# carrier.net
KiCad netlist of a schematic drawn in Altium Designer
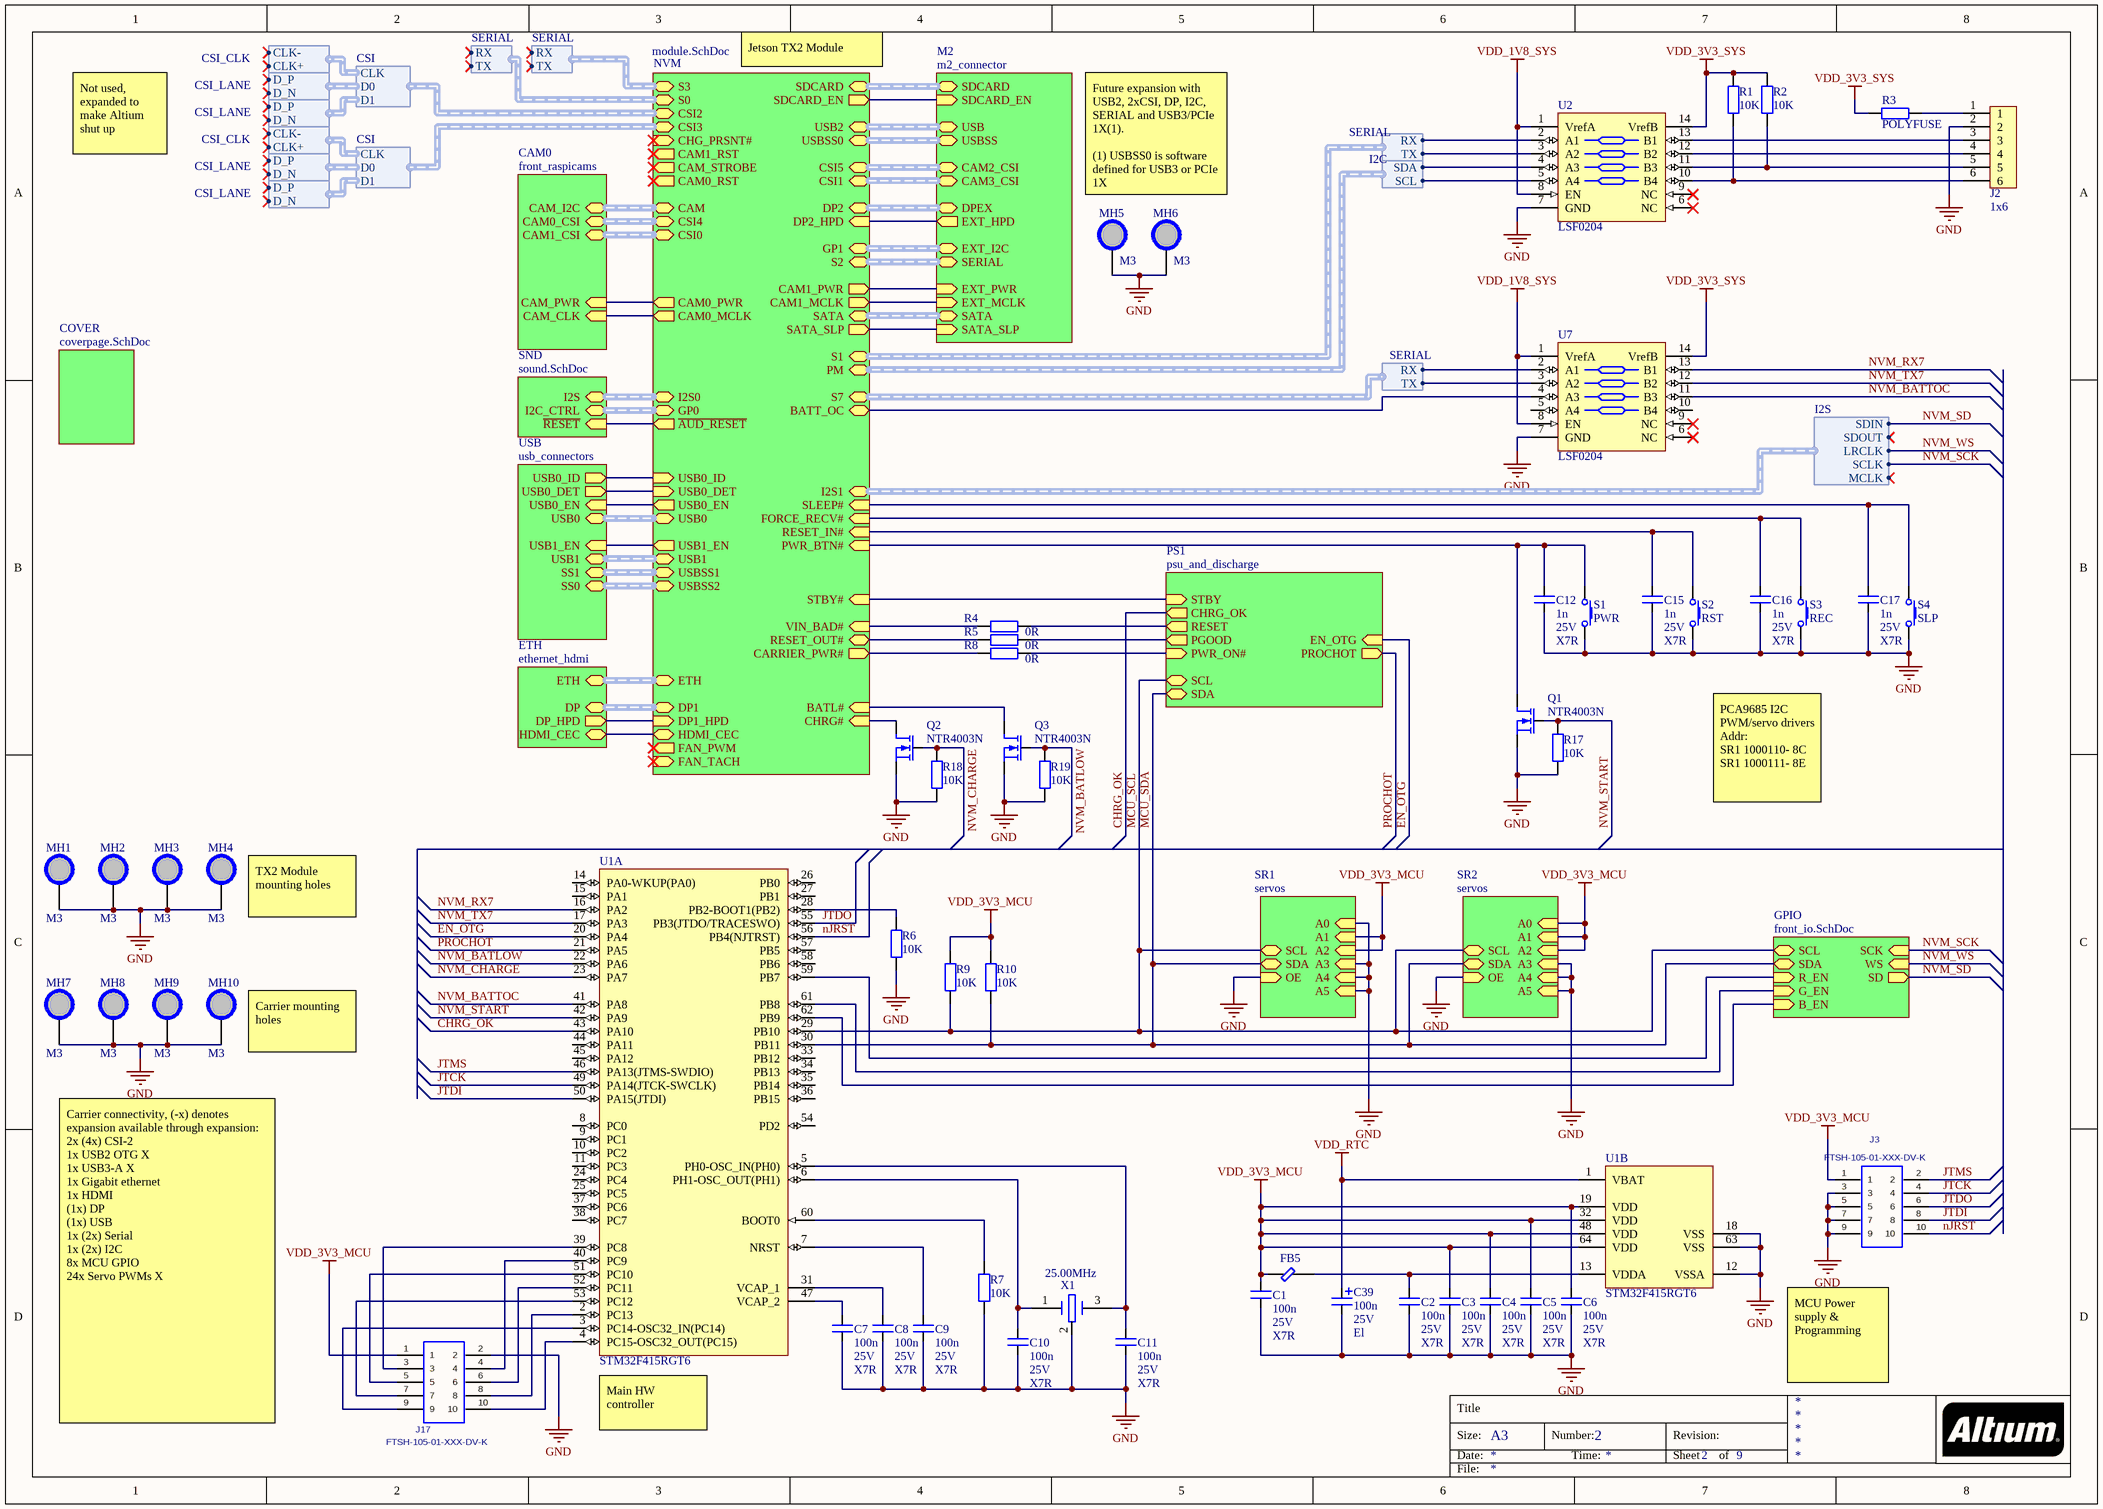
[diagram p0: carrier.SchDoc]

(export (version "E")
  (design (tool "Eeschema 10.0.6"))
  (components
    (comp (ref "C1")
      (value "100n")
      (footprint "C1005[0402]")
      (description "Capacitor")
      (fields (field (name "VOLTAGE") "25V") (field (name "TYPE") "X7R") (field (name "Comment") "cap"))
      (libsource (lib "gpa_passives") (part "cap"))
    )
    (comp (ref "C2")
      (value "100n")
      (footprint "C1005[0402]")
      (description "Capacitor")
      (fields (field (name "VOLTAGE") "25V") (field (name "TYPE") "X7R") (field (name "Comment") "cap"))
      (libsource (lib "gpa_passives") (part "cap"))
    )
    (comp (ref "C3")
      (value "100n")
      (footprint "C1005[0402]")
      (description "Capacitor")
      (fields (field (name "VOLTAGE") "25V") (field (name "TYPE") "X7R") (field (name "Comment") "cap"))
      (libsource (lib "gpa_passives") (part "cap"))
    )
    (comp (ref "C4")
      (value "100n")
      (footprint "C1005[0402]")
      (description "Capacitor")
      (fields (field (name "VOLTAGE") "25V") (field (name "TYPE") "X7R") (field (name "Comment") "cap"))
      (libsource (lib "gpa_passives") (part "cap"))
    )
    (comp (ref "C5")
      (value "100n")
      (footprint "C1005[0402]")
      (description "Capacitor")
      (fields (field (name "VOLTAGE") "25V") (field (name "TYPE") "X7R") (field (name "Comment") "cap"))
      (libsource (lib "gpa_passives") (part "cap"))
    )
    (comp (ref "C6")
      (value "100n")
      (footprint "C1005[0402]")
      (description "Capacitor")
      (fields (field (name "VOLTAGE") "25V") (field (name "TYPE") "X7R") (field (name "Comment") "cap"))
      (libsource (lib "gpa_passives") (part "cap"))
    )
    (comp (ref "C7")
      (value "100n")
      (footprint "C1005[0402]")
      (description "Capacitor")
      (fields (field (name "VOLTAGE") "25V") (field (name "TYPE") "X7R") (field (name "Comment") "cap"))
      (libsource (lib "gpa_passives") (part "cap"))
    )
    (comp (ref "C8")
      (value "100n")
      (footprint "C1005[0402]")
      (description "Capacitor")
      (fields (field (name "VOLTAGE") "25V") (field (name "TYPE") "X7R") (field (name "Comment") "cap"))
      (libsource (lib "gpa_passives") (part "cap"))
    )
    (comp (ref "C9")
      (value "100n")
      (footprint "C1005[0402]")
      (description "Capacitor")
      (fields (field (name "VOLTAGE") "25V") (field (name "TYPE") "X7R") (field (name "Comment") "cap"))
      (libsource (lib "gpa_passives") (part "cap"))
    )
    (comp (ref "C10")
      (value "100n")
      (footprint "C1005[0402]")
      (description "Capacitor")
      (fields (field (name "VOLTAGE") "25V") (field (name "TYPE") "X7R") (field (name "Comment") "cap"))
      (libsource (lib "gpa_passives") (part "cap"))
    )
    (comp (ref "C11")
      (value "100n")
      (footprint "C1005[0402]")
      (description "Capacitor")
      (fields (field (name "VOLTAGE") "25V") (field (name "TYPE") "X7R") (field (name "Comment") "cap"))
      (libsource (lib "gpa_passives") (part "cap"))
    )
    (comp (ref "C12")
      (value "1n")
      (footprint "C1005[0402]")
      (description "Capacitor")
      (fields (field (name "VOLTAGE") "25V") (field (name "TYPE") "X7R") (field (name "Comment") "cap"))
      (libsource (lib "gpa_passives") (part "cap"))
    )
    (comp (ref "C15")
      (value "1n")
      (footprint "C1005[0402]")
      (description "Capacitor")
      (fields (field (name "VOLTAGE") "25V") (field (name "TYPE") "X7R") (field (name "Comment") "cap"))
      (libsource (lib "gpa_passives") (part "cap"))
    )
    (comp (ref "C16")
      (value "1n")
      (footprint "C1005[0402]")
      (description "Capacitor")
      (fields (field (name "VOLTAGE") "25V") (field (name "TYPE") "X7R") (field (name "Comment") "cap"))
      (libsource (lib "gpa_passives") (part "cap"))
    )
    (comp (ref "C17")
      (value "1n")
      (footprint "C1005[0402]")
      (description "Capacitor")
      (fields (field (name "VOLTAGE") "25V") (field (name "TYPE") "X7R") (field (name "Comment") "cap"))
      (libsource (lib "gpa_passives") (part "cap"))
    )
    (comp (ref "C39")
      (value "100n")
      (footprint "SC_FCS0H473ZFTBR24")
      (description "Polarized capacitor")
      (fields (field (name "VOLTAGE") "25V") (field (name "TYPE") "El") (field (name "Comment") "pcap"))
      (libsource (lib "gpa_passives") (part "pcap"))
    )
    (comp (ref "FB5")
      (value "2506036007Y3")
      (footprint "FBC1608X07N")
      (description "Ferrite bead")
      (libsource (lib "gpa_passives") (part "ferrite_bead"))
    )
    (comp (ref "J2")
      (value "1x6")
      (footprint "hdr_100mil_1x6")
      (libsource (lib "gpa_connectors") (part "header_1x6"))
    )
    (comp (ref "J3")
      (value "FTSH-105-01-XXX-DV-K")
      (footprint "FTSH-105-01-XXX-DV-K")
      (description "TERMINAL STRIP, .050\"(1.27mm) PITCH, 10 PINS, KEYED")
      (fields (field (name "MANUFACTURER") "SAMTEC") (field (name "CREATED") "November 30, 2016 - Wendy Xin"))
      (libsource (lib "FTSH-105-01-XXX-DV-K") (part "FTSH-105-01-XXX-DV-K"))
    )
    (comp (ref "J17")
      (value "FTSH-105-01-XXX-DV-K")
      (footprint "FTSH-105-01-XXX-DV-K")
      (description "TERMINAL STRIP, .050\"(1.27mm) PITCH, 10 PINS, KEYED")
      (fields (field (name "MANUFACTURER") "SAMTEC") (field (name "CREATED") "November 30, 2016 - Wendy Xin"))
      (libsource (lib "FTSH-105-01-XXX-DV-K") (part "FTSH-105-01-XXX-DV-K"))
    )
    (comp (ref "MH1")
      (value "M3")
      (footprint "m2_pan_loose_round")
      (libsource (lib "gpa_mounting") (part "mounting_hole"))
    )
    (comp (ref "MH2")
      (value "M3")
      (footprint "m2_pan_loose_round")
      (libsource (lib "gpa_mounting") (part "mounting_hole"))
    )
    (comp (ref "MH3")
      (value "M3")
      (footprint "m2_pan_loose_round")
      (libsource (lib "gpa_mounting") (part "mounting_hole"))
    )
    (comp (ref "MH4")
      (value "M3")
      (footprint "m2_pan_loose_round")
      (libsource (lib "gpa_mounting") (part "mounting_hole"))
    )
    (comp (ref "MH5")
      (value "M3")
      (footprint "m2_pan_loose_round")
      (libsource (lib "gpa_mounting") (part "mounting_hole"))
    )
    (comp (ref "MH6")
      (value "M3")
      (footprint "m2_pan_loose_round")
      (libsource (lib "gpa_mounting") (part "mounting_hole"))
    )
    (comp (ref "MH7")
      (value "M3")
      (footprint "m2_pan_loose_round")
      (libsource (lib "gpa_mounting") (part "mounting_hole"))
    )
    (comp (ref "MH8")
      (value "M3")
      (footprint "m2_pan_loose_round")
      (libsource (lib "gpa_mounting") (part "mounting_hole"))
    )
    (comp (ref "MH9")
      (value "M3")
      (footprint "m2_pan_loose_round")
      (libsource (lib "gpa_mounting") (part "mounting_hole"))
    )
    (comp (ref "MH10")
      (value "M3")
      (footprint "m2_pan_loose_round")
      (libsource (lib "gpa_mounting") (part "mounting_hole"))
    )
    (comp (ref "Q1")
      (value "NTR4003N")
      (footprint "NCH_SOT95P237X110-3N")
      (libsource (lib "gpa_actives") (part "nch_mosfet"))
    )
    (comp (ref "Q2")
      (value "NTR4003N")
      (footprint "NCH_SOT95P237X110-3N")
      (libsource (lib "gpa_actives") (part "nch_mosfet"))
    )
    (comp (ref "Q3")
      (value "NTR4003N")
      (footprint "NCH_SOT95P237X110-3N")
      (libsource (lib "gpa_actives") (part "nch_mosfet"))
    )
    (comp (ref "R1")
      (value "10K")
      (footprint "R1005[0402]")
      (description "Resistor")
      (fields (field (name "Comment") "res"))
      (libsource (lib "gpa_passives") (part "res"))
    )
    (comp (ref "R2")
      (value "10K")
      (footprint "R1005[0402]")
      (description "Resistor")
      (fields (field (name "Comment") "res"))
      (libsource (lib "gpa_passives") (part "res"))
    )
    (comp (ref "R3")
      (value "POLYFUSE")
      (footprint "R1005[0402]")
      (description "Resistor")
      (fields (field (name "Comment") "res"))
      (libsource (lib "") (part "res_2"))
    )
    (comp (ref "R4")
      (value "0R")
      (footprint "R1005[0402]")
      (description "Resistor")
      (fields (field (name "Comment") "res"))
      (libsource (lib "gpa_passives") (part "res"))
    )
    (comp (ref "R5")
      (value "0R")
      (footprint "R1005[0402]")
      (description "Resistor")
      (fields (field (name "Comment") "res"))
      (libsource (lib "gpa_passives") (part "res"))
    )
    (comp (ref "R6")
      (value "10K")
      (footprint "R1005[0402]")
      (description "Resistor")
      (fields (field (name "Comment") "res"))
      (libsource (lib "") (part "res_1"))
    )
    (comp (ref "R7")
      (value "10K")
      (footprint "R1005[0402]")
      (description "Resistor")
      (fields (field (name "Comment") "res"))
      (libsource (lib "") (part "res_1"))
    )
    (comp (ref "R8")
      (value "0R")
      (footprint "R1005[0402]")
      (description "Resistor")
      (fields (field (name "Comment") "res"))
      (libsource (lib "gpa_passives") (part "res"))
    )
    (comp (ref "R9")
      (value "10K")
      (footprint "R1005[0402]")
      (description "Resistor")
      (fields (field (name "Comment") "res"))
      (libsource (lib "") (part "res_1"))
    )
    (comp (ref "R10")
      (value "10K")
      (footprint "R1005[0402]")
      (description "Resistor")
      (fields (field (name "Comment") "res"))
      (libsource (lib "") (part "res_1"))
    )
    (comp (ref "R17")
      (value "10K")
      (footprint "R1005[0402]")
      (description "Resistor")
      (fields (field (name "Comment") "res"))
      (libsource (lib "") (part "res_1"))
    )
    (comp (ref "R18")
      (value "10K")
      (footprint "R1005[0402]")
      (description "Resistor")
      (fields (field (name "Comment") "res"))
      (libsource (lib "") (part "res_1"))
    )
    (comp (ref "R19")
      (value "10K")
      (footprint "R1005[0402]")
      (description "Resistor")
      (fields (field (name "Comment") "res"))
      (libsource (lib "") (part "res_1"))
    )
    (comp (ref "S1")
      (value "btn")
      (footprint "SW_6MM_TACT")
      (fields (field (name "TEXT") "PWR"))
      (libsource (lib "gpa_passives") (part "btn"))
    )
    (comp (ref "S2")
      (value "btn")
      (footprint "SW_6MM_TACT")
      (fields (field (name "TEXT") "RST"))
      (libsource (lib "gpa_passives") (part "btn"))
    )
    (comp (ref "S3")
      (value "btn")
      (footprint "SW_6MM_TACT")
      (fields (field (name "TEXT") "REC"))
      (libsource (lib "gpa_passives") (part "btn"))
    )
    (comp (ref "S4")
      (value "btn")
      (footprint "SW_6MM_TACT")
      (fields (field (name "TEXT") "SLP"))
      (libsource (lib "gpa_passives") (part "btn"))
    )
    (comp (ref "U1")
      (value "STM32F415RGT6")
      (footprint "STM-LQFP64_N")
      (fields (field (name "MANUFACTURER") "STMicroelectronics"))
      (libsource (lib "STMicroelectronics STM32 F4") (part "STM32F415RGT6"))
    )
    (comp (ref "U2")
      (value "LSF0204")
      (footprint "TI_TSOP65P640X120-14N")
      (libsource (lib "gpa_ti") (part "lsf0204"))
    )
    (comp (ref "U7")
      (value "LSF0204")
      (footprint "TI_TSOP65P640X120-14N")
      (libsource (lib "gpa_ti") (part "lsf0204"))
    )
    (comp (ref "X1")
      (value "25.00MHz")
      (footprint "FA-238")
      (description "Crystal with shield")
      (fields (field (name "Comment") "crystal_shielded"))
      (libsource (lib "gpa_passives") (part "crystal_shielded"))
    )
  )
  (nets
    (net (code "6") (name "/BATL#") (class "Default")
      (node (ref "Q3") (pin "D") (pinfunction "D_D") (pintype "passive"))
    )
    (net (code "7") (name "/BATT_OC") (class "Default")
      (node (ref "U7") (pin "4") (pinfunction "A3_4") (pintype "bidirectional"))
    )
    (net (code "8") (name "/B_EN") (class "Default")
      (node (ref "U1") (pin "62") (pinfunction "PB9_62") (pintype "bidirectional"))
    )
    (net (code "21") (name "/CARRIER_PWR#") (class "Default")
      (node (ref "R8") (pin "1") (pinfunction "1_1") (pintype "passive"))
    )
    (net (code "23") (name "/CHRG#") (class "Default")
      (node (ref "Q2") (pin "D") (pinfunction "D_D") (pintype "passive"))
    )
    (net (code "24") (name "/CHRG_OK") (class "Default")
      (node (ref "U1") (pin "43") (pinfunction "PA10_43") (pintype "bidirectional"))
    )
    (net (code "29") (name "/EN_OTG") (class "Default")
      (node (ref "U1") (pin "20") (pinfunction "PA4_20") (pintype "bidirectional"))
    )
    (net (code "35") (name "/FORCE_RECV#") (class "Default")
      (node (ref "C16") (pin "2") (pinfunction "2_2") (pintype "passive"))
      (node (ref "S3") (pin "1") (pinfunction "1_1") (pintype "passive"))
    )
    (net (code "37") (name "/G_EN") (class "Default")
      (node (ref "U1") (pin "61") (pinfunction "PB8_61") (pintype "bidirectional"))
    )
    (net (code "40") (name "/JTCK") (class "Default")
      (node (ref "J3") (pin "4") (pinfunction "4_4") (pintype "passive"))
      (node (ref "U1") (pin "49") (pinfunction "PA14(JTCK-SWCLK)_49") (pintype "bidirectional"))
    )
    (net (code "41") (name "/JTDI") (class "Default")
      (node (ref "J3") (pin "8") (pinfunction "8_8") (pintype "passive"))
      (node (ref "U1") (pin "50") (pinfunction "PA15(JTDI)_50") (pintype "bidirectional"))
    )
    (net (code "42") (name "/JTDO") (class "Default")
      (node (ref "J3") (pin "6") (pinfunction "6_6") (pintype "passive"))
      (node (ref "U1") (pin "55") (pinfunction "PB3(JTDO/TRACESWO)_55") (pintype "bidirectional"))
    )
    (net (code "43") (name "/JTMS") (class "Default")
      (node (ref "J3") (pin "2") (pinfunction "2_2") (pintype "passive"))
      (node (ref "U1") (pin "46") (pinfunction "PA13(JTMS-SWDIO)_46") (pintype "bidirectional"))
    )
    (net (code "44") (name "/MCU_SCL") (class "Default")
      (node (ref "R9") (pin "1") (pinfunction "1_1") (pintype "passive"))
      (node (ref "U1") (pin "29") (pinfunction "PB10_29") (pintype "bidirectional"))
    )
    (net (code "45") (name "/MCU_SDA") (class "Default")
      (node (ref "R10") (pin "1") (pinfunction "1_1") (pintype "passive"))
      (node (ref "U1") (pin "30") (pinfunction "PB11_30") (pintype "bidirectional"))
    )
    (net (code "46") (name "/NVM_BATLOW") (class "Default")
      (node (ref "Q3") (pin "G") (pinfunction "G_G") (pintype "passive"))
      (node (ref "R19") (pin "2") (pinfunction "2_2") (pintype "passive"))
      (node (ref "U1") (pin "22") (pinfunction "PA6_22") (pintype "bidirectional"))
    )
    (net (code "47") (name "/NVM_BATTOC") (class "Default")
      (node (ref "U1") (pin "41") (pinfunction "PA8_41") (pintype "bidirectional"))
      (node (ref "U7") (pin "11") (pinfunction "B3_11") (pintype "bidirectional"))
    )
    (net (code "48") (name "/NVM_CHARGE") (class "Default")
      (node (ref "Q2") (pin "G") (pinfunction "G_G") (pintype "passive"))
      (node (ref "R18") (pin "2") (pinfunction "2_2") (pintype "passive"))
      (node (ref "U1") (pin "23") (pinfunction "PA7_23") (pintype "bidirectional"))
    )
    (net (code "49") (name "/NVM_RX7") (class "Default")
      (node (ref "U1") (pin "16") (pinfunction "PA2_16") (pintype "bidirectional"))
      (node (ref "U7") (pin "13") (pinfunction "B1_13") (pintype "bidirectional"))
    )
    (net (code "52") (name "/NVM_START") (class "Default")
      (node (ref "Q1") (pin "G") (pinfunction "G_G") (pintype "passive"))
      (node (ref "R17") (pin "2") (pinfunction "2_2") (pintype "passive"))
      (node (ref "U1") (pin "42") (pinfunction "PA9_42") (pintype "bidirectional"))
    )
    (net (code "53") (name "/NVM_TX7") (class "Default")
      (node (ref "U1") (pin "17") (pinfunction "PA3_17") (pintype "bidirectional"))
      (node (ref "U7") (pin "12") (pinfunction "B2_12") (pintype "bidirectional"))
    )
    (net (code "55") (name "/PGOOD") (class "Default")
      (node (ref "R5") (pin "2") (pinfunction "2_2") (pintype "passive"))
    )
    (net (code "56") (name "/PROCHOT") (class "Default")
      (node (ref "U1") (pin "21") (pinfunction "PA5_21") (pintype "bidirectional"))
    )
    (net (code "57") (name "/PWR_BTN#") (class "Default")
      (node (ref "C12") (pin "2") (pinfunction "2_2") (pintype "passive"))
      (node (ref "Q1") (pin "D") (pinfunction "D_D") (pintype "passive"))
      (node (ref "S1") (pin "1") (pinfunction "1_1") (pintype "passive"))
    )
    (net (code "58") (name "/PWR_ON#") (class "Default")
      (node (ref "R8") (pin "2") (pinfunction "2_2") (pintype "passive"))
    )
    (net (code "59") (name "/RESET") (class "Default")
      (node (ref "R4") (pin "2") (pinfunction "2_2") (pintype "passive"))
    )
    (net (code "60") (name "/RESET_IN#") (class "Default")
      (node (ref "C15") (pin "2") (pinfunction "2_2") (pintype "passive"))
      (node (ref "S2") (pin "1") (pinfunction "1_1") (pintype "passive"))
    )
    (net (code "61") (name "/RESET_OUT#") (class "Default")
      (node (ref "R5") (pin "1") (pinfunction "1_1") (pintype "passive"))
    )
    (net (code "62") (name "/R_EN") (class "Default")
      (node (ref "U1") (pin "59") (pinfunction "PB7_59") (pintype "bidirectional"))
    )
    (net (code "69") (name "/SLEEP#") (class "Default")
      (node (ref "C17") (pin "2") (pinfunction "2_2") (pintype "passive"))
      (node (ref "S4") (pin "1") (pinfunction "1_1") (pintype "passive"))
    )
    (net (code "81") (name "/VIN_BAD#") (class "Default")
      (node (ref "R4") (pin "1") (pinfunction "1_1") (pintype "passive"))
    )
    (net (code "82") (name "/nJRST") (class "Default")
      (node (ref "J3") (pin "10") (pinfunction "10_10") (pintype "passive"))
      (node (ref "U1") (pin "56") (pinfunction "PB4(NJTRST)_56") (pintype "bidirectional"))
    )
    (net (code "87") (name "GND") (class "Default")
      (node (ref "C1") (pin "2") (pinfunction "2_2") (pintype "passive"))
      (node (ref "C10") (pin "2") (pinfunction "2_2") (pintype "passive"))
      (node (ref "C11") (pin "2") (pinfunction "2_2") (pintype "passive"))
      (node (ref "C12") (pin "1") (pinfunction "1_1") (pintype "passive"))
      (node (ref "C15") (pin "1") (pinfunction "1_1") (pintype "passive"))
      (node (ref "C16") (pin "1") (pinfunction "1_1") (pintype "passive"))
      (node (ref "C17") (pin "1") (pinfunction "1_1") (pintype "passive"))
      (node (ref "C2") (pin "2") (pinfunction "2_2") (pintype "passive"))
      (node (ref "C3") (pin "2") (pinfunction "2_2") (pintype "passive"))
      (node (ref "C39") (pin "2") (pinfunction "2_2") (pintype "passive"))
      (node (ref "C4") (pin "2") (pinfunction "2_2") (pintype "passive"))
      (node (ref "C5") (pin "2") (pinfunction "2_2") (pintype "passive"))
      (node (ref "C6") (pin "2") (pinfunction "2_2") (pintype "passive"))
      (node (ref "C7") (pin "2") (pinfunction "2_2") (pintype "passive"))
      (node (ref "C8") (pin "2") (pinfunction "2_2") (pintype "passive"))
      (node (ref "C9") (pin "2") (pinfunction "2_2") (pintype "passive"))
      (node (ref "J17") (pin "2") (pinfunction "2_2") (pintype "passive"))
      (node (ref "J2") (pin "2") (pinfunction "2_2") (pintype "passive"))
      (node (ref "J3") (pin "3") (pinfunction "3_3") (pintype "passive"))
      (node (ref "J3") (pin "5") (pinfunction "5_5") (pintype "passive"))
      (node (ref "J3") (pin "7") (pinfunction "7_7") (pintype "passive"))
      (node (ref "J3") (pin "9") (pinfunction "9_9") (pintype "passive"))
      (node (ref "MH1") (pin "1") (pinfunction "1_1") (pintype "passive"))
      (node (ref "MH10") (pin "1") (pinfunction "1_1") (pintype "passive"))
      (node (ref "MH2") (pin "1") (pinfunction "1_1") (pintype "passive"))
      (node (ref "MH3") (pin "1") (pinfunction "1_1") (pintype "passive"))
      (node (ref "MH4") (pin "1") (pinfunction "1_1") (pintype "passive"))
      (node (ref "MH5") (pin "1") (pinfunction "1_1") (pintype "passive"))
      (node (ref "MH6") (pin "1") (pinfunction "1_1") (pintype "passive"))
      (node (ref "MH7") (pin "1") (pinfunction "1_1") (pintype "passive"))
      (node (ref "MH8") (pin "1") (pinfunction "1_1") (pintype "passive"))
      (node (ref "MH9") (pin "1") (pinfunction "1_1") (pintype "passive"))
      (node (ref "Q1") (pin "S") (pinfunction "S_S") (pintype "passive"))
      (node (ref "Q2") (pin "S") (pinfunction "S_S") (pintype "passive"))
      (node (ref "Q3") (pin "S") (pinfunction "S_S") (pintype "passive"))
      (node (ref "R17") (pin "1") (pinfunction "1_1") (pintype "passive"))
      (node (ref "R18") (pin "1") (pinfunction "1_1") (pintype "passive"))
      (node (ref "R19") (pin "1") (pinfunction "1_1") (pintype "passive"))
      (node (ref "R6") (pin "1") (pinfunction "1_1") (pintype "passive"))
      (node (ref "R7") (pin "1") (pinfunction "1_1") (pintype "passive"))
      (node (ref "S1") (pin "2") (pinfunction "2_2") (pintype "passive"))
      (node (ref "S2") (pin "2") (pinfunction "2_2") (pintype "passive"))
      (node (ref "S3") (pin "2") (pinfunction "2_2") (pintype "passive"))
      (node (ref "S4") (pin "2") (pinfunction "2_2") (pintype "passive"))
      (node (ref "U1") (pin "12") (pinfunction "VSSA_12") (pintype "power_in"))
      (node (ref "U1") (pin "18") (pinfunction "VSS_18") (pintype "power_in"))
      (node (ref "U1") (pin "63") (pinfunction "VSS_63") (pintype "power_in"))
      (node (ref "U2") (pin "7") (pinfunction "GND_7") (pintype "power_in"))
      (node (ref "U7") (pin "7") (pinfunction "GND_7") (pintype "power_in"))
      (node (ref "X1") (pin "2") (pinfunction "2_2") (pintype "passive"))
    )
    (net (code "88") (name "Net-(J2-Pad1)") (class "Default")
      (node (ref "J2") (pin "1") (pinfunction "1_1") (pintype "passive"))
      (node (ref "R3") (pin "1") (pinfunction "1_1") (pintype "passive"))
    )
    (net (code "89") (name "Net-(U1A-BOOT0)") (class "Default")
      (node (ref "R7") (pin "2") (pinfunction "2_2") (pintype "passive"))
      (node (ref "U1") (pin "60") (pinfunction "BOOT0_60") (pintype "input"))
    )
    (net (code "90") (name "Net-(U1A-NRST)") (class "Default")
      (node (ref "C9") (pin "1") (pinfunction "1_1") (pintype "passive"))
      (node (ref "U1") (pin "7") (pinfunction "NRST_7") (pintype "bidirectional"))
    )
    (net (code "91") (name "Net-(U1A-PB2-BOOT1(PB2))") (class "Default")
      (node (ref "R6") (pin "2") (pinfunction "2_2") (pintype "passive"))
      (node (ref "U1") (pin "28") (pinfunction "PB2-BOOT1(PB2)_28") (pintype "bidirectional"))
    )
    (net (code "92") (name "Net-(U1A-PC8)") (class "Default")
      (node (ref "J17") (pin "3") (pinfunction "3_3") (pintype "passive"))
      (node (ref "U1") (pin "39") (pinfunction "PC8_39") (pintype "bidirectional"))
    )
    (net (code "93") (name "Net-(U1A-PC9)") (class "Default")
      (node (ref "J17") (pin "4") (pinfunction "4_4") (pintype "passive"))
      (node (ref "U1") (pin "40") (pinfunction "PC9_40") (pintype "bidirectional"))
    )
    (net (code "94") (name "Net-(U1A-PC10)") (class "Default")
      (node (ref "J17") (pin "5") (pinfunction "5_5") (pintype "passive"))
      (node (ref "U1") (pin "51") (pinfunction "PC10_51") (pintype "bidirectional"))
    )
    (net (code "95") (name "Net-(U1A-PC11)") (class "Default")
      (node (ref "J17") (pin "6") (pinfunction "6_6") (pintype "passive"))
      (node (ref "U1") (pin "52") (pinfunction "PC11_52") (pintype "bidirectional"))
    )
    (net (code "96") (name "Net-(U1A-PC12)") (class "Default")
      (node (ref "J17") (pin "7") (pinfunction "7_7") (pintype "passive"))
      (node (ref "U1") (pin "53") (pinfunction "PC12_53") (pintype "bidirectional"))
    )
    (net (code "97") (name "Net-(U1A-PC13)") (class "Default")
      (node (ref "J17") (pin "8") (pinfunction "8_8") (pintype "passive"))
      (node (ref "U1") (pin "2") (pinfunction "PC13_2") (pintype "bidirectional"))
    )
    (net (code "98") (name "Net-(U1A-PC14-OSC32_IN(PC14))") (class "Default")
      (node (ref "J17") (pin "9") (pinfunction "9_9") (pintype "passive"))
      (node (ref "U1") (pin "3") (pinfunction "PC14-OSC32_IN(PC14)_3") (pintype "bidirectional"))
    )
    (net (code "99") (name "Net-(U1A-PC15-OSC32_OUT(PC15))") (class "Default")
      (node (ref "J17") (pin "10") (pinfunction "10_10") (pintype "passive"))
      (node (ref "U1") (pin "4") (pinfunction "PC15-OSC32_OUT(PC15)_4") (pintype "bidirectional"))
    )
    (net (code "100") (name "Net-(U1A-PH0-OSC_IN(PH0))") (class "Default")
      (node (ref "C11") (pin "1") (pinfunction "1_1") (pintype "passive"))
      (node (ref "U1") (pin "5") (pinfunction "PH0-OSC_IN(PH0)_5") (pintype "bidirectional"))
      (node (ref "X1") (pin "3") (pinfunction "3_3") (pintype "passive"))
    )
    (net (code "101") (name "Net-(U1A-PH1-OSC_OUT(PH1))") (class "Default")
      (node (ref "C10") (pin "1") (pinfunction "1_1") (pintype "passive"))
      (node (ref "U1") (pin "6") (pinfunction "PH1-OSC_OUT(PH1)_6") (pintype "bidirectional"))
      (node (ref "X1") (pin "1") (pinfunction "1_1") (pintype "passive"))
    )
    (net (code "102") (name "Net-(U1A-VCAP_1)") (class "Default")
      (node (ref "C8") (pin "1") (pinfunction "1_1") (pintype "passive"))
      (node (ref "U1") (pin "31") (pinfunction "VCAP_1_31") (pintype "power_in"))
    )
    (net (code "103") (name "Net-(U1A-VCAP_2)") (class "Default")
      (node (ref "C7") (pin "1") (pinfunction "1_1") (pintype "passive"))
      (node (ref "U1") (pin "47") (pinfunction "VCAP_2_47") (pintype "power_in"))
    )
    (net (code "104") (name "Net-(U1B-VDDA)") (class "Default")
      (node (ref "C2") (pin "1") (pinfunction "1_1") (pintype "passive"))
      (node (ref "FB5") (pin "2") (pinfunction "2_2") (pintype "passive"))
      (node (ref "U1") (pin "13") (pinfunction "VDDA_13") (pintype "power_in"))
    )
    (net (code "105") (name "Net-(U2-B1)") (class "Default")
      (node (ref "J2") (pin "3") (pinfunction "3_3") (pintype "passive"))
      (node (ref "U2") (pin "13") (pinfunction "B1_13") (pintype "bidirectional"))
    )
    (net (code "106") (name "Net-(U2-B2)") (class "Default")
      (node (ref "J2") (pin "4") (pinfunction "4_4") (pintype "passive"))
      (node (ref "U2") (pin "12") (pinfunction "B2_12") (pintype "bidirectional"))
    )
    (net (code "107") (name "Net-(U2-B3)") (class "Default")
      (node (ref "J2") (pin "5") (pinfunction "5_5") (pintype "passive"))
      (node (ref "R2") (pin "1") (pinfunction "1_1") (pintype "passive"))
      (node (ref "U2") (pin "11") (pinfunction "B3_11") (pintype "bidirectional"))
    )
    (net (code "108") (name "Net-(U2-B4)") (class "Default")
      (node (ref "J2") (pin "6") (pinfunction "6_6") (pintype "passive"))
      (node (ref "R1") (pin "1") (pinfunction "1_1") (pintype "passive"))
      (node (ref "U2") (pin "10") (pinfunction "B4_10") (pintype "bidirectional"))
    )
    (net (code "109") (name "VDD_1V8_SYS") (class "Default")
      (node (ref "U2") (pin "1") (pinfunction "VrefA_1") (pintype "power_in"))
      (node (ref "U2") (pin "8") (pinfunction "EN_8") (pintype "input"))
      (node (ref "U7") (pin "1") (pinfunction "VrefA_1") (pintype "power_in"))
      (node (ref "U7") (pin "8") (pinfunction "EN_8") (pintype "input"))
    )
    (net (code "110") (name "VDD_3V3_MCU") (class "Default")
      (node (ref "C1") (pin "1") (pinfunction "1_1") (pintype "passive"))
      (node (ref "C3") (pin "1") (pinfunction "1_1") (pintype "passive"))
      (node (ref "C4") (pin "1") (pinfunction "1_1") (pintype "passive"))
      (node (ref "C5") (pin "1") (pinfunction "1_1") (pintype "passive"))
      (node (ref "C6") (pin "1") (pinfunction "1_1") (pintype "passive"))
      (node (ref "FB5") (pin "1") (pinfunction "1_1") (pintype "passive"))
      (node (ref "J17") (pin "1") (pinfunction "1_1") (pintype "passive"))
      (node (ref "J3") (pin "1") (pinfunction "1_1") (pintype "passive"))
      (node (ref "R10") (pin "2") (pinfunction "2_2") (pintype "passive"))
      (node (ref "R9") (pin "2") (pinfunction "2_2") (pintype "passive"))
      (node (ref "U1") (pin "19") (pinfunction "VDD_19") (pintype "power_in"))
      (node (ref "U1") (pin "32") (pinfunction "VDD_32") (pintype "power_in"))
      (node (ref "U1") (pin "48") (pinfunction "VDD_48") (pintype "power_in"))
      (node (ref "U1") (pin "64") (pinfunction "VDD_64") (pintype "power_in"))
    )
    (net (code "111") (name "VDD_3V3_SYS") (class "Default")
      (node (ref "R1") (pin "2") (pinfunction "2_2") (pintype "passive"))
      (node (ref "R2") (pin "2") (pinfunction "2_2") (pintype "passive"))
      (node (ref "R3") (pin "2") (pinfunction "2_2") (pintype "passive"))
      (node (ref "U2") (pin "14") (pinfunction "VrefB_14") (pintype "power_in"))
      (node (ref "U7") (pin "14") (pinfunction "VrefB_14") (pintype "power_in"))
    )
    (net (code "112") (name "VDD_RTC") (class "Default")
      (node (ref "C39") (pin "1") (pinfunction "1_1") (pintype "passive"))
      (node (ref "U1") (pin "1") (pinfunction "VBAT_1") (pintype "power_in"))
    )
    (net (code "113") (name "unconnected-(U1A-PA0-WKUP(PA0)-Pad14)") (class "Default")
      (node (ref "U1") (pin "14") (pinfunction "PA0-WKUP(PA0)_14") (pintype "bidirectional"))
    )
    (net (code "114") (name "unconnected-(U1A-PA1-Pad15)") (class "Default")
      (node (ref "U1") (pin "15") (pinfunction "PA1_15") (pintype "bidirectional"))
    )
    (net (code "115") (name "unconnected-(U1A-PA11-Pad44)") (class "Default")
      (node (ref "U1") (pin "44") (pinfunction "PA11_44") (pintype "bidirectional"))
    )
    (net (code "116") (name "unconnected-(U1A-PA12-Pad45)") (class "Default")
      (node (ref "U1") (pin "45") (pinfunction "PA12_45") (pintype "bidirectional"))
    )
    (net (code "117") (name "unconnected-(U1A-PB0-Pad26)") (class "Default")
      (node (ref "U1") (pin "26") (pinfunction "PB0_26") (pintype "bidirectional"))
    )
    (net (code "118") (name "unconnected-(U1A-PB1-Pad27)") (class "Default")
      (node (ref "U1") (pin "27") (pinfunction "PB1_27") (pintype "bidirectional"))
    )
    (net (code "119") (name "unconnected-(U1A-PB5-Pad57)") (class "Default")
      (node (ref "U1") (pin "57") (pinfunction "PB5_57") (pintype "bidirectional"))
    )
    (net (code "120") (name "unconnected-(U1A-PB6-Pad58)") (class "Default")
      (node (ref "U1") (pin "58") (pinfunction "PB6_58") (pintype "bidirectional"))
    )
    (net (code "121") (name "unconnected-(U1A-PB12-Pad33)") (class "Default")
      (node (ref "U1") (pin "33") (pinfunction "PB12_33") (pintype "bidirectional"))
    )
    (net (code "122") (name "unconnected-(U1A-PB13-Pad34)") (class "Default")
      (node (ref "U1") (pin "34") (pinfunction "PB13_34") (pintype "bidirectional"))
    )
    (net (code "123") (name "unconnected-(U1A-PB14-Pad35)") (class "Default")
      (node (ref "U1") (pin "35") (pinfunction "PB14_35") (pintype "bidirectional"))
    )
    (net (code "124") (name "unconnected-(U1A-PB15-Pad36)") (class "Default")
      (node (ref "U1") (pin "36") (pinfunction "PB15_36") (pintype "bidirectional"))
    )
    (net (code "125") (name "unconnected-(U1A-PC0-Pad8)") (class "Default")
      (node (ref "U1") (pin "8") (pinfunction "PC0_8") (pintype "bidirectional"))
    )
    (net (code "126") (name "unconnected-(U1A-PC1-Pad9)") (class "Default")
      (node (ref "U1") (pin "9") (pinfunction "PC1_9") (pintype "bidirectional"))
    )
    (net (code "127") (name "unconnected-(U1A-PC2-Pad10)") (class "Default")
      (node (ref "U1") (pin "10") (pinfunction "PC2_10") (pintype "bidirectional"))
    )
    (net (code "128") (name "unconnected-(U1A-PC3-Pad11)") (class "Default")
      (node (ref "U1") (pin "11") (pinfunction "PC3_11") (pintype "bidirectional"))
    )
    (net (code "129") (name "unconnected-(U1A-PC4-Pad24)") (class "Default")
      (node (ref "U1") (pin "24") (pinfunction "PC4_24") (pintype "bidirectional"))
    )
    (net (code "130") (name "unconnected-(U1A-PC5-Pad25)") (class "Default")
      (node (ref "U1") (pin "25") (pinfunction "PC5_25") (pintype "bidirectional"))
    )
    (net (code "131") (name "unconnected-(U1A-PC6-Pad37)") (class "Default")
      (node (ref "U1") (pin "37") (pinfunction "PC6_37") (pintype "bidirectional"))
    )
    (net (code "132") (name "unconnected-(U1A-PC7-Pad38)") (class "Default")
      (node (ref "U1") (pin "38") (pinfunction "PC7_38") (pintype "bidirectional"))
    )
    (net (code "133") (name "unconnected-(U1A-PD2-Pad54)") (class "Default")
      (node (ref "U1") (pin "54") (pinfunction "PD2_54") (pintype "bidirectional"))
    )
    (net (code "134") (name "unconnected-(U2-A1-Pad2)") (class "Default")
      (node (ref "U2") (pin "2") (pinfunction "A1_2") (pintype "bidirectional"))
    )
    (net (code "135") (name "unconnected-(U2-A2-Pad3)") (class "Default")
      (node (ref "U2") (pin "3") (pinfunction "A2_3") (pintype "bidirectional"))
    )
    (net (code "136") (name "unconnected-(U2-A3-Pad4)") (class "Default")
      (node (ref "U2") (pin "4") (pinfunction "A3_4") (pintype "bidirectional"))
    )
    (net (code "137") (name "unconnected-(U2-A4-Pad5)") (class "Default")
      (node (ref "U2") (pin "5") (pinfunction "A4_5") (pintype "bidirectional"))
    )
    (net (code "138") (name "unconnected-(U2-NC-Pad6)") (class "Default")
      (node (ref "U2") (pin "6") (pinfunction "NC_6") (pintype "input+no_connect"))
    )
    (net (code "139") (name "unconnected-(U2-NC-Pad9)") (class "Default")
      (node (ref "U2") (pin "9") (pinfunction "NC_9") (pintype "input+no_connect"))
    )
    (net (code "140") (name "unconnected-(U7-A1-Pad2)") (class "Default")
      (node (ref "U7") (pin "2") (pinfunction "A1_2") (pintype "bidirectional"))
    )
    (net (code "141") (name "unconnected-(U7-A2-Pad3)") (class "Default")
      (node (ref "U7") (pin "3") (pinfunction "A2_3") (pintype "bidirectional"))
    )
    (net (code "142") (name "unconnected-(U7-A4-Pad5)") (class "Default")
      (node (ref "U7") (pin "5") (pinfunction "A4_5") (pintype "bidirectional"))
    )
    (net (code "143") (name "unconnected-(U7-B4-Pad10)") (class "Default")
      (node (ref "U7") (pin "10") (pinfunction "B4_10") (pintype "bidirectional"))
    )
    (net (code "144") (name "unconnected-(U7-NC-Pad6)") (class "Default")
      (node (ref "U7") (pin "6") (pinfunction "NC_6") (pintype "input+no_connect"))
    )
    (net (code "145") (name "unconnected-(U7-NC-Pad9)") (class "Default")
      (node (ref "U7") (pin "9") (pinfunction "NC_9") (pintype "input+no_connect"))
    )
  )
)
